# M8-GPIO.net
KiCad netlist of a schematic drawn in EAGLE
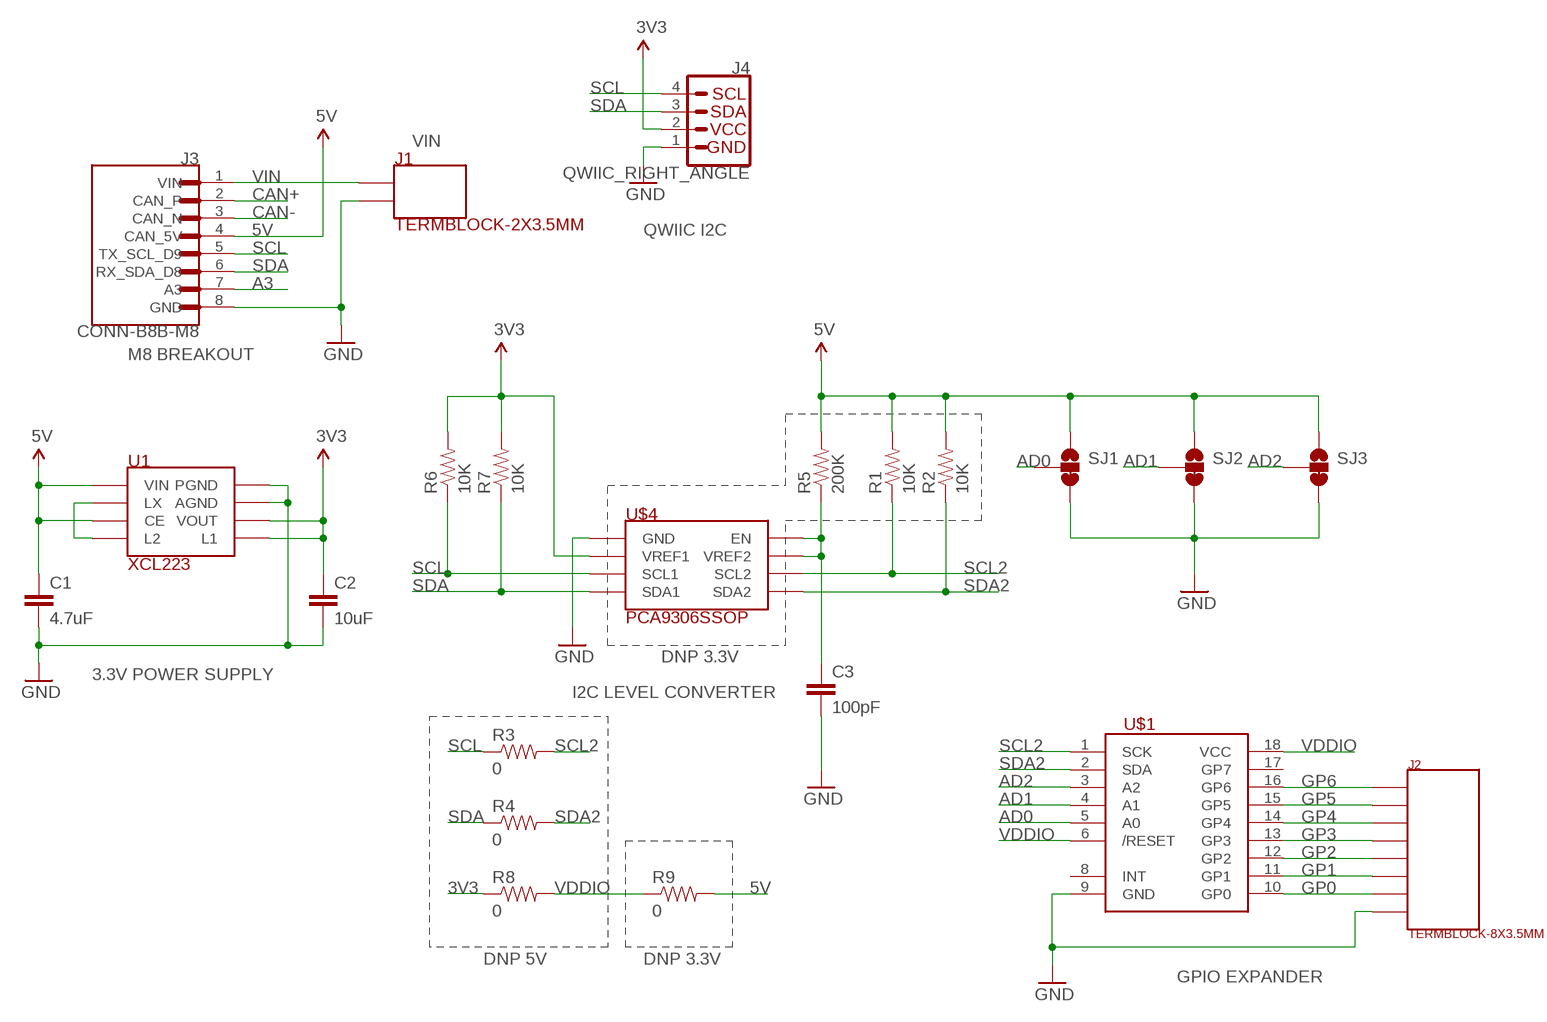
[diagram p0: schematic, sheet 1]

(export (version "E")
  (design (tool "Eeschema 10.0.6"))
  (components
    (comp (ref "C1")
      (value "4.7uF")
      (footprint "eagle-import:0603-CAP")
      (libsource (lib "eagle-import") (part "CAP-4.7UF-0603"))
    )
    (comp (ref "C2")
      (value "10uF")
      (footprint "eagle-import:0603-CAP")
      (libsource (lib "eagle-import") (part "CAP-10UF-0603"))
    )
    (comp (ref "C3")
      (value "100pF")
      (footprint "eagle-import:0603-CAP")
      (libsource (lib "eagle-import") (part "CAP-100PF-0603"))
    )
    (comp (ref "J1")
      (value "TERMBLOCK-2X3.5MM")
      (footprint "eagle-import:TERMBLOCK-2X3.5MM")
      (libsource (lib "eagle-import") (part "TERMBLOCK-2X3.5MM"))
    )
    (comp (ref "J2")
      (value "TERMBLOCK-8X3.5MM")
      (footprint "eagle-import:TERMBLOCK-8X3.5MM")
      (libsource (lib "eagle-import") (part "TERMBLOCK-8X3.5MM"))
    )
    (comp (ref "J3")
      (value "CONN-B8B-M8")
      (footprint "eagle-import:JST_B8B-PH-SM4-TB(LF)(SN)")
      (libsource (lib "eagle-import") (part "CONN-B8B-M8"))
    )
    (comp (ref "J4")
      (value "QWIIC_RIGHT_ANGLE")
      (footprint "eagle-import:JST04_1MM_RA")
      (libsource (lib "eagle-import") (part "QWIIC_CONNECTORJS-1MM"))
    )
    (comp (ref "R1")
      (value "10K")
      (footprint "eagle-import:0603-RES")
      (libsource (lib "eagle-import") (part "RES-10K-06030603"))
    )
    (comp (ref "R2")
      (value "10K")
      (footprint "eagle-import:0603-RES")
      (libsource (lib "eagle-import") (part "RES-10K-06030603"))
    )
    (comp (ref "R3")
      (value "0")
      (footprint "eagle-import:0603-RES")
      (libsource (lib "eagle-import") (part "RES-0-0603"))
    )
    (comp (ref "R4")
      (value "0")
      (footprint "eagle-import:0603-RES")
      (libsource (lib "eagle-import") (part "RES-0-0603"))
    )
    (comp (ref "R5")
      (value "200K")
      (footprint "eagle-import:0603-RES")
      (libsource (lib "eagle-import") (part "RES-200K-0603"))
    )
    (comp (ref "R6")
      (value "10K")
      (footprint "eagle-import:0603-RES")
      (libsource (lib "eagle-import") (part "RES-10K-06030603"))
    )
    (comp (ref "R7")
      (value "10K")
      (footprint "eagle-import:0603-RES")
      (libsource (lib "eagle-import") (part "RES-10K-06030603"))
    )
    (comp (ref "R8")
      (value "0")
      (footprint "eagle-import:0603-RES")
      (libsource (lib "eagle-import") (part "RES-0-0603"))
    )
    (comp (ref "R9")
      (value "0")
      (footprint "eagle-import:0603-RES")
      (libsource (lib "eagle-import") (part "RES-0-0603"))
    )
    (comp (ref "SJ1")
      (value "JUMPER-PAD-3-2OF3_NC_BY_TRACE_SMALL")
      (footprint "eagle-import:PAD-JUMPER-3-2OF3_NC_BY_TRACE_NO_SILK")
      (libsource (lib "eagle-import") (part "JUMPER-PAD-3-2OF3_NC_BY_TRACE_SMALL"))
    )
    (comp (ref "SJ2")
      (value "JUMPER-PAD-3-2OF3_NC_BY_TRACE_SMALL")
      (footprint "eagle-import:PAD-JUMPER-3-2OF3_NC_BY_TRACE_NO_SILK")
      (libsource (lib "eagle-import") (part "JUMPER-PAD-3-2OF3_NC_BY_TRACE_SMALL"))
    )
    (comp (ref "SJ3")
      (value "JUMPER-PAD-3-2OF3_NC_BY_TRACE_SMALL")
      (footprint "eagle-import:PAD-JUMPER-3-2OF3_NC_BY_TRACE_NO_SILK")
      (libsource (lib "eagle-import") (part "JUMPER-PAD-3-2OF3_NC_BY_TRACE_SMALL"))
    )
    (comp (ref "U$1")
      (value "MCP23008")
      (footprint "eagle-import:SOIC-18-W-MAXIM")
      (libsource (lib "eagle-import") (part "MCP23008"))
    )
    (comp (ref "U$4")
      (value "PCA9306SSOP")
      (footprint "eagle-import:8-SSOP-TI")
      (libsource (lib "eagle-import") (part "PCA9306SSOP"))
    )
    (comp (ref "U1")
      (value "XCL223")
      (footprint "eagle-import:REG-XCL223-LESS-CREAM")
      (libsource (lib "eagle-import") (part "REG-XCL223"))
    )
  )
  (nets
    (net (code "1") (name "/A3") (class "Default")
      (node (ref "J3") (pin "7") (pinfunction "A3_7") (pintype "passive"))
    )
    (net (code "2") (name "/AD0") (class "Default")
      (node (ref "SJ1") (pin "2") (pinfunction "2_2") (pintype "passive"))
      (node (ref "U$1") (pin "5") (pinfunction "A0_5") (pintype "bidirectional"))
    )
    (net (code "3") (name "/AD1") (class "Default")
      (node (ref "SJ2") (pin "2") (pinfunction "2_2") (pintype "passive"))
      (node (ref "U$1") (pin "4") (pinfunction "A1_4") (pintype "input"))
    )
    (net (code "4") (name "/AD2") (class "Default")
      (node (ref "SJ3") (pin "2") (pinfunction "2_2") (pintype "passive"))
      (node (ref "U$1") (pin "3") (pinfunction "A2_3") (pintype "input"))
    )
    (net (code "5") (name "/CAN+") (class "Default")
      (node (ref "J3") (pin "2") (pinfunction "CAN_P_2") (pintype "passive"))
    )
    (net (code "6") (name "/CAN-") (class "Default")
      (node (ref "J3") (pin "3") (pinfunction "CAN_N_3") (pintype "passive"))
    )
    (net (code "7") (name "/GP0") (class "Default")
      (node (ref "J2") (pin "7") (pinfunction "7_7") (pintype "passive"))
      (node (ref "U$1") (pin "10") (pinfunction "GP0_10") (pintype "bidirectional"))
    )
    (net (code "8") (name "/GP1") (class "Default")
      (node (ref "J2") (pin "6") (pinfunction "6_6") (pintype "passive"))
      (node (ref "U$1") (pin "11") (pinfunction "GP1_11") (pintype "bidirectional"))
    )
    (net (code "9") (name "/GP2") (class "Default")
      (node (ref "J2") (pin "5") (pinfunction "5_5") (pintype "passive"))
      (node (ref "U$1") (pin "12") (pinfunction "GP2_12") (pintype "bidirectional"))
    )
    (net (code "10") (name "/GP3") (class "Default")
      (node (ref "J2") (pin "4") (pinfunction "4_4") (pintype "passive"))
      (node (ref "U$1") (pin "13") (pinfunction "GP3_13") (pintype "bidirectional"))
    )
    (net (code "11") (name "/GP4") (class "Default")
      (node (ref "J2") (pin "3") (pinfunction "3_3") (pintype "passive"))
      (node (ref "U$1") (pin "14") (pinfunction "GP4_14") (pintype "bidirectional"))
    )
    (net (code "12") (name "/GP5") (class "Default")
      (node (ref "J2") (pin "2") (pinfunction "2_2") (pintype "passive"))
      (node (ref "U$1") (pin "15") (pinfunction "GP5_15") (pintype "bidirectional"))
    )
    (net (code "13") (name "/GP6") (class "Default")
      (node (ref "J2") (pin "1") (pinfunction "1_1") (pintype "passive"))
      (node (ref "U$1") (pin "16") (pinfunction "GP6_16") (pintype "bidirectional"))
    )
    (net (code "14") (name "/SCL") (class "Default")
      (node (ref "J3") (pin "5") (pinfunction "TX_SCL_D9_5") (pintype "passive"))
      (node (ref "J4") (pin "4") (pinfunction "4_4") (pintype "passive"))
      (node (ref "R3") (pin "1") (pinfunction "1_1") (pintype "passive"))
      (node (ref "R6") (pin "1") (pinfunction "1_1") (pintype "passive"))
      (node (ref "U$4") (pin "3") (pinfunction "SCL1_3") (pintype "bidirectional"))
    )
    (net (code "15") (name "/SCL2") (class "Default")
      (node (ref "R1") (pin "1") (pinfunction "1_1") (pintype "passive"))
      (node (ref "R3") (pin "2") (pinfunction "2_2") (pintype "passive"))
      (node (ref "U$1") (pin "1") (pinfunction "SCK_1") (pintype "input"))
      (node (ref "U$4") (pin "6") (pinfunction "SCL2_6") (pintype "bidirectional"))
    )
    (net (code "16") (name "/SDA") (class "Default")
      (node (ref "J3") (pin "6") (pinfunction "RX_SDA_D8_6") (pintype "passive"))
      (node (ref "J4") (pin "3") (pinfunction "3_3") (pintype "passive"))
      (node (ref "R4") (pin "1") (pinfunction "1_1") (pintype "passive"))
      (node (ref "R7") (pin "1") (pinfunction "1_1") (pintype "passive"))
      (node (ref "U$4") (pin "4") (pinfunction "SDA1_4") (pintype "bidirectional"))
    )
    (net (code "17") (name "/SDA2") (class "Default")
      (node (ref "R2") (pin "1") (pinfunction "1_1") (pintype "passive"))
      (node (ref "R4") (pin "2") (pinfunction "2_2") (pintype "passive"))
      (node (ref "U$1") (pin "2") (pinfunction "SDA_2") (pintype "bidirectional"))
      (node (ref "U$4") (pin "5") (pinfunction "SDA2_5") (pintype "bidirectional"))
    )
    (net (code "18") (name "/VDDIO") (class "Default")
      (node (ref "R8") (pin "2") (pinfunction "2_2") (pintype "passive"))
      (node (ref "R9") (pin "1") (pinfunction "1_1") (pintype "passive"))
      (node (ref "U$1") (pin "18") (pinfunction "VCC_18") (pintype "passive"))
      (node (ref "U$1") (pin "6") (pinfunction "/RESET_6") (pintype "input"))
    )
    (net (code "19") (name "/VIN") (class "Default")
      (node (ref "J1") (pin "1") (pinfunction "1_1") (pintype "passive"))
      (node (ref "J3") (pin "1") (pinfunction "VIN_1") (pintype "passive"))
    )
    (net (code "20") (name "3V3") (class "Default")
      (node (ref "C2") (pin "1") (pinfunction "1_1") (pintype "passive"))
      (node (ref "J4") (pin "2") (pinfunction "2_2") (pintype "power_in"))
      (node (ref "R6") (pin "2") (pinfunction "2_2") (pintype "passive"))
      (node (ref "R7") (pin "2") (pinfunction "2_2") (pintype "passive"))
      (node (ref "R8") (pin "1") (pinfunction "1_1") (pintype "passive"))
      (node (ref "U$4") (pin "2") (pinfunction "VREF1_2") (pintype "power_in"))
      (node (ref "U1") (pin "3") (pinfunction "VOUT_3") (pintype "passive"))
      (node (ref "U1") (pin "7") (pinfunction "L1_7") (pintype "passive"))
    )
    (net (code "21") (name "5V") (class "Default")
      (node (ref "C1") (pin "1") (pinfunction "1_1") (pintype "passive"))
      (node (ref "J3") (pin "4") (pinfunction "CAN_5V_4") (pintype "passive"))
      (node (ref "R1") (pin "2") (pinfunction "2_2") (pintype "passive"))
      (node (ref "R2") (pin "2") (pinfunction "2_2") (pintype "passive"))
      (node (ref "R5") (pin "2") (pinfunction "2_2") (pintype "passive"))
      (node (ref "R9") (pin "2") (pinfunction "2_2") (pintype "passive"))
      (node (ref "SJ1") (pin "1") (pinfunction "1_1") (pintype "passive"))
      (node (ref "SJ2") (pin "1") (pinfunction "1_1") (pintype "passive"))
      (node (ref "SJ3") (pin "1") (pinfunction "1_1") (pintype "passive"))
      (node (ref "U1") (pin "4") (pinfunction "CE_4") (pintype "input"))
      (node (ref "U1") (pin "6") (pinfunction "VIN_6") (pintype "power_in"))
    )
    (net (code "22") (name "GND") (class "Default")
      (node (ref "C1") (pin "2") (pinfunction "2_2") (pintype "passive"))
      (node (ref "C2") (pin "2") (pinfunction "2_2") (pintype "passive"))
      (node (ref "C3") (pin "2") (pinfunction "2_2") (pintype "passive"))
      (node (ref "J1") (pin "2") (pinfunction "2_2") (pintype "passive"))
      (node (ref "J2") (pin "8") (pinfunction "8_8") (pintype "passive"))
      (node (ref "J3") (pin "8") (pinfunction "GND_8") (pintype "passive"))
      (node (ref "J4") (pin "1") (pinfunction "1_1") (pintype "power_in"))
      (node (ref "SJ1") (pin "3") (pinfunction "3_3") (pintype "passive"))
      (node (ref "SJ2") (pin "3") (pinfunction "3_3") (pintype "passive"))
      (node (ref "SJ3") (pin "3") (pinfunction "3_3") (pintype "passive"))
      (node (ref "U$1") (pin "9") (pinfunction "GND_9") (pintype "passive"))
      (node (ref "U$4") (pin "1") (pinfunction "GND_1") (pintype "passive"))
      (node (ref "U1") (pin "1") (pinfunction "PGND_1") (pintype "passive"))
      (node (ref "U1") (pin "2") (pinfunction "AGND_2") (pintype "passive"))
    )
    (net (code "23") (name "Net-(U$4-EN)") (class "Default")
      (node (ref "C3") (pin "1") (pinfunction "1_1") (pintype "passive"))
      (node (ref "R5") (pin "1") (pinfunction "1_1") (pintype "passive"))
      (node (ref "U$4") (pin "7") (pinfunction "VREF2_7") (pintype "input"))
      (node (ref "U$4") (pin "8") (pinfunction "EN_8") (pintype "input"))
    )
    (net (code "24") (name "Net-(U1-L2)") (class "Default")
      (node (ref "U1") (pin "5") (pinfunction "LX_5") (pintype "passive"))
      (node (ref "U1") (pin "8") (pinfunction "L2_8") (pintype "passive"))
    )
    (net (code "25") (name "unconnected-(U$1-GP7-Pad17)") (class "Default")
      (node (ref "U$1") (pin "17") (pinfunction "GP7_17") (pintype "bidirectional"))
    )
    (net (code "26") (name "unconnected-(U$1-INT-Pad8)") (class "Default")
      (node (ref "U$1") (pin "8") (pinfunction "INT_8") (pintype "output"))
    )
  )
)
